# USB_OTG_FS.net
KiCad netlist of a schematic drawn in Altium Designer
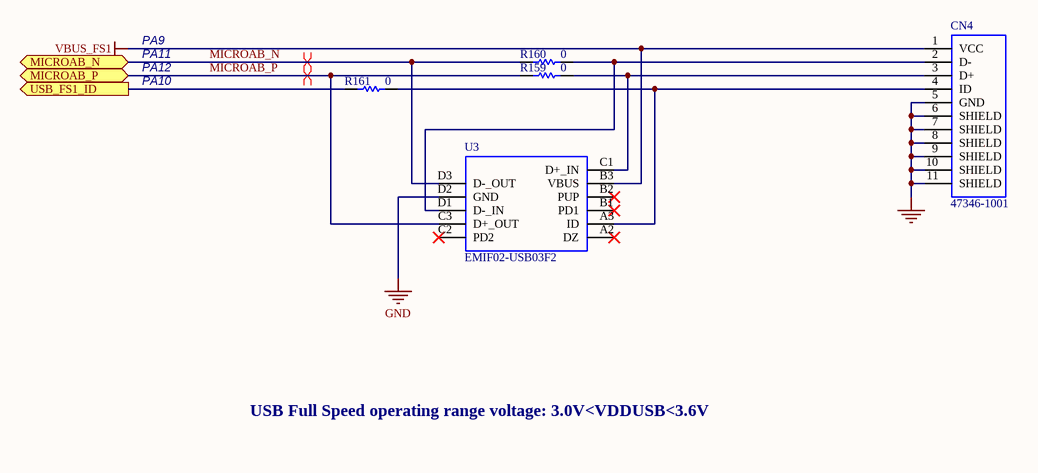
[diagram p0: USB_OTG_FS.SchDoc]

(export (version "E")
  (design (tool "Eeschema 10.0.6"))
  (components
    (comp (ref "CN4")
      (value "47346-1001")
      (footprint "47346-0001")
      (description "MOLEX - 47346-1001 - MULTIPOLE CONNECTOR")
      (fields (field (name "MOUSER PART NUMBER") "538-47346-1001"))
      (libsource (lib "47346-1001") (part "47346-1001"))
    )
    (comp (ref "R159")
      (value "0")
      (footprint "RES - 0402")
      (description "Resistor")
      (fields (field (name "PUBLISHER") "Altium Limited"))
      (libsource (lib "Miscellaneous Devices") (part "Res1"))
    )
    (comp (ref "R160")
      (value "0")
      (footprint "RES - 0402")
      (description "Resistor")
      (fields (field (name "PUBLISHER") "Altium Limited"))
      (libsource (lib "Miscellaneous Devices") (part "Res1"))
    )
    (comp (ref "R161")
      (value "0")
      (footprint "RES - 0402")
      (description "Resistor")
      (fields (field (name "PUBLISHER") "Altium Limited"))
      (libsource (lib "Miscellaneous Devices") (part "Res1"))
    )
    (comp (ref "U3")
      (value "EMIF02-USB03F2")
      (footprint "BGA11C50P3X4_144X194X72")
      (description "New STMicroelectronics EMIF02-USB03F2 EMI Filter & ESD Protector")
      (fields (field (name "RS PART NUMBER") "1658173"))
      (libsource (lib "EMIF02-USB03F2") (part "EMIF02-USB03F2"))
    )
  )
  (nets
    (net (code "1") (name "/MICROAB_N") (class "Default")
      (node (ref "R160") (pin "2") (pinfunction "2_2") (pintype "passive"))
      (node (ref "U3") (pin "D3") (pinfunction "D-_OUT_D3") (pintype "passive"))
    )
    (net (code "2") (name "/MICROAB_P") (class "Default")
      (node (ref "R159") (pin "2") (pinfunction "2_2") (pintype "passive"))
      (node (ref "U3") (pin "C3") (pinfunction "D+_OUT_C3") (pintype "passive"))
    )
    (net (code "3") (name "/USB_FS1_ID") (class "Default")
      (node (ref "R161") (pin "2") (pinfunction "2_2") (pintype "passive"))
    )
    (net (code "4") (name "GND") (class "Default")
      (node (ref "CN4") (pin "10") (pinfunction "SHIELD_10") (pintype "passive"))
      (node (ref "CN4") (pin "11") (pinfunction "SHIELD_11") (pintype "passive"))
      (node (ref "CN4") (pin "5") (pinfunction "GND_5") (pintype "passive"))
      (node (ref "CN4") (pin "6") (pinfunction "SHIELD_6") (pintype "passive"))
      (node (ref "CN4") (pin "7") (pinfunction "SHIELD_7") (pintype "passive"))
      (node (ref "CN4") (pin "8") (pinfunction "SHIELD_8") (pintype "passive"))
      (node (ref "CN4") (pin "9") (pinfunction "SHIELD_9") (pintype "passive"))
      (node (ref "U3") (pin "D2") (pinfunction "GND_D2") (pintype "passive"))
    )
    (net (code "5") (name "Net-(CN4-D+)") (class "Default")
      (node (ref "CN4") (pin "3") (pinfunction "D+_3") (pintype "passive"))
      (node (ref "R159") (pin "1") (pinfunction "1_1") (pintype "passive"))
      (node (ref "U3") (pin "C1") (pinfunction "D+_IN_C1") (pintype "passive"))
    )
    (net (code "6") (name "Net-(CN4-D-)") (class "Default")
      (node (ref "CN4") (pin "2") (pinfunction "D-_2") (pintype "passive"))
      (node (ref "R160") (pin "1") (pinfunction "1_1") (pintype "passive"))
      (node (ref "U3") (pin "D1") (pinfunction "D-_IN_D1") (pintype "passive"))
    )
    (net (code "7") (name "Net-(CN4-ID)") (class "Default")
      (node (ref "CN4") (pin "4") (pinfunction "ID_4") (pintype "passive"))
      (node (ref "R161") (pin "1") (pinfunction "1_1") (pintype "passive"))
      (node (ref "U3") (pin "A3") (pinfunction "ID_A3") (pintype "passive"))
    )
    (net (code "8") (name "VBUS_FS1") (class "Default")
      (node (ref "CN4") (pin "1") (pinfunction "VCC_1") (pintype "passive"))
      (node (ref "U3") (pin "B3") (pinfunction "VBUS_B3") (pintype "passive"))
    )
    (net (code "9") (name "unconnected-(U3-DZ-PadA2)") (class "Default")
      (node (ref "U3") (pin "A2") (pinfunction "DZ_A2") (pintype "passive+no_connect"))
    )
    (net (code "10") (name "unconnected-(U3-PD1-PadB1)") (class "Default")
      (node (ref "U3") (pin "B1") (pinfunction "PD1_B1") (pintype "passive+no_connect"))
    )
    (net (code "11") (name "unconnected-(U3-PD2-PadC2)") (class "Default")
      (node (ref "U3") (pin "C2") (pinfunction "PD2_C2") (pintype "passive+no_connect"))
    )
    (net (code "12") (name "unconnected-(U3-PUP-PadB2)") (class "Default")
      (node (ref "U3") (pin "B2") (pinfunction "PUP_B2") (pintype "passive+no_connect"))
    )
  )
)
